# 04-LED-YELLOW.net
KiCad netlist of a schematic drawn in Altium Designer
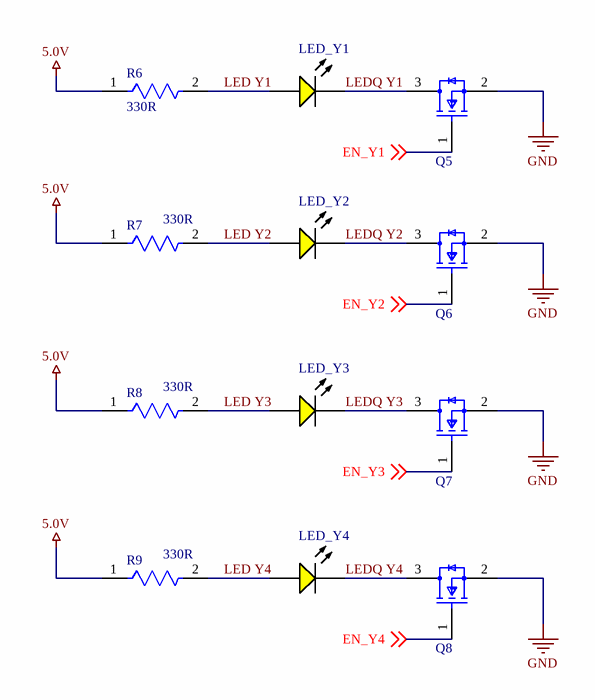
[diagram p0: 04-LED-YELLOW.SchDoc]

(export (version "E")
  (design (tool "Eeschema 10.0.6"))
  (components
    (comp (ref "LED_Y1")
      (value "SML-LX1206YC-TR")
      (footprint "LUMX-SML-LX1206YC-TR_V")
      (description "Yellow LED, Water Clear Len, 585 nm, 2.1 V, -40 to 85 degC, 2-Pin SMD, RoHS, Tape and Reel")
      (fields (field (name "MANUFACTURER") "Lumex"))
      (libsource (lib "Altium Content Vault") (part "LED-YELLOW-AK-2"))
    )
    (comp (ref "LED_Y2")
      (value "SML-LX1206YC-TR")
      (footprint "LUMX-SML-LX1206YC-TR_V")
      (description "Yellow LED, Water Clear Len, 585 nm, 2.1 V, -40 to 85 degC, 2-Pin SMD, RoHS, Tape and Reel")
      (fields (field (name "MANUFACTURER") "Lumex"))
      (libsource (lib "Altium Content Vault") (part "LED-YELLOW-AK-2"))
    )
    (comp (ref "LED_Y3")
      (value "SML-LX1206YC-TR")
      (footprint "LUMX-SML-LX1206YC-TR_V")
      (description "Yellow LED, Water Clear Len, 585 nm, 2.1 V, -40 to 85 degC, 2-Pin SMD, RoHS, Tape and Reel")
      (fields (field (name "MANUFACTURER") "Lumex"))
      (libsource (lib "Altium Content Vault") (part "LED-YELLOW-AK-2"))
    )
    (comp (ref "LED_Y4")
      (value "SML-LX1206YC-TR")
      (footprint "LUMX-SML-LX1206YC-TR_V")
      (description "Yellow LED, Water Clear Len, 585 nm, 2.1 V, -40 to 85 degC, 2-Pin SMD, RoHS, Tape and Reel")
      (fields (field (name "MANUFACTURER") "Lumex"))
      (libsource (lib "Altium Content Vault") (part "LED-YELLOW-AK-2"))
    )
    (comp (ref "Q5")
      (value "2N7002-7-F")
      (footprint "FP-SOT23-MFG")
      (description "MOSFET N-CH 60V 115MA SOT23-3")
      (fields (field (name "VOLTAGE") "60V"))
      (libsource (lib "Altium Content Vault") (part "3b9c635fedb024a5347a57b145af9cc"))
    )
    (comp (ref "Q6")
      (value "2N7002-7-F")
      (footprint "FP-SOT23-MFG")
      (description "MOSFET N-CH 60V 115MA SOT23-3")
      (fields (field (name "VOLTAGE") "60V"))
      (libsource (lib "Altium Content Vault") (part "3b9c635fedb024a5347a57b145af9cc"))
    )
    (comp (ref "Q7")
      (value "2N7002-7-F")
      (footprint "FP-SOT23-MFG")
      (description "MOSFET N-CH 60V 115MA SOT23-3")
      (fields (field (name "VOLTAGE") "60V"))
      (libsource (lib "Altium Content Vault") (part "3b9c635fedb024a5347a57b145af9cc"))
    )
    (comp (ref "Q8")
      (value "2N7002-7-F")
      (footprint "FP-SOT23-MFG")
      (description "MOSFET N-CH 60V 115MA SOT23-3")
      (fields (field (name "VOLTAGE") "60V"))
      (libsource (lib "Altium Content Vault") (part "3b9c635fedb024a5347a57b145af9cc"))
    )
    (comp (ref "R6")
      (value "CRCW1206330RFKEA")
      (footprint "FP-CRCW1206-e3-IPC_A")
      (description "RES Thick Film, 330Ω, 1%, 0.25W, 100ppm/°C, 1206")
      (fields (field (name "TOLERANCE") "1%") (field (name "RESISTANCE") "330R"))
      (libsource (lib "Altium Content Vault") (part "1029c3af85768c4190bb7ad29bc67b5"))
    )
    (comp (ref "R7")
      (value "CRCW1206330RFKEA")
      (footprint "FP-CRCW1206-e3-IPC_A")
      (description "RES Thick Film, 330Ω, 1%, 0.25W, 100ppm/°C, 1206")
      (fields (field (name "TOLERANCE") "1%") (field (name "RESISTANCE") "330R"))
      (libsource (lib "Altium Content Vault") (part "1029c3af85768c4190bb7ad29bc67b5"))
    )
    (comp (ref "R8")
      (value "CRCW1206330RFKEA")
      (footprint "FP-CRCW1206-e3-IPC_A")
      (description "RES Thick Film, 330Ω, 1%, 0.25W, 100ppm/°C, 1206")
      (fields (field (name "TOLERANCE") "1%") (field (name "RESISTANCE") "330R"))
      (libsource (lib "Altium Content Vault") (part "1029c3af85768c4190bb7ad29bc67b5"))
    )
    (comp (ref "R9")
      (value "CRCW1206330RFKEA")
      (footprint "FP-CRCW1206-e3-IPC_A")
      (description "RES Thick Film, 330Ω, 1%, 0.25W, 100ppm/°C, 1206")
      (fields (field (name "TOLERANCE") "1%") (field (name "RESISTANCE") "330R"))
      (libsource (lib "Altium Content Vault") (part "1029c3af85768c4190bb7ad29bc67b5"))
    )
  )
  (nets
    (net (code "1") (name "/LED Y1") (class "Default")
      (node (ref "LED_Y1") (pin "1") (pinfunction "A_1") (pintype "passive"))
      (node (ref "R6") (pin "2") (pinfunction "2_2") (pintype "passive"))
    )
    (net (code "2") (name "/LED Y2") (class "Default")
      (node (ref "LED_Y2") (pin "1") (pinfunction "A_1") (pintype "passive"))
      (node (ref "R7") (pin "2") (pinfunction "2_2") (pintype "passive"))
    )
    (net (code "3") (name "/LED Y3") (class "Default")
      (node (ref "LED_Y3") (pin "1") (pinfunction "A_1") (pintype "passive"))
      (node (ref "R8") (pin "2") (pinfunction "2_2") (pintype "passive"))
    )
    (net (code "4") (name "/LED Y4") (class "Default")
      (node (ref "LED_Y4") (pin "1") (pinfunction "A_1") (pintype "passive"))
      (node (ref "R9") (pin "2") (pinfunction "2_2") (pintype "passive"))
    )
    (net (code "5") (name "/LEDQ Y1") (class "Default")
      (node (ref "LED_Y1") (pin "2") (pinfunction "K_2") (pintype "passive"))
      (node (ref "Q5") (pin "3") (pinfunction "D_3") (pintype "passive"))
    )
    (net (code "6") (name "/LEDQ Y2") (class "Default")
      (node (ref "LED_Y2") (pin "2") (pinfunction "K_2") (pintype "passive"))
      (node (ref "Q6") (pin "3") (pinfunction "D_3") (pintype "passive"))
    )
    (net (code "7") (name "/LEDQ Y3") (class "Default")
      (node (ref "LED_Y3") (pin "2") (pinfunction "K_2") (pintype "passive"))
      (node (ref "Q7") (pin "3") (pinfunction "D_3") (pintype "passive"))
    )
    (net (code "8") (name "/LEDQ Y4") (class "Default")
      (node (ref "LED_Y4") (pin "2") (pinfunction "K_2") (pintype "passive"))
      (node (ref "Q8") (pin "3") (pinfunction "D_3") (pintype "passive"))
    )
    (net (code "9") (name "5.0V") (class "Default")
      (node (ref "R6") (pin "1") (pinfunction "1_1") (pintype "passive"))
      (node (ref "R7") (pin "1") (pinfunction "1_1") (pintype "passive"))
      (node (ref "R8") (pin "1") (pinfunction "1_1") (pintype "passive"))
      (node (ref "R9") (pin "1") (pinfunction "1_1") (pintype "passive"))
    )
    (net (code "10") (name "EN_Y1") (class "Default")
      (node (ref "Q5") (pin "1") (pinfunction "G_1") (pintype "passive"))
    )
    (net (code "11") (name "EN_Y2") (class "Default")
      (node (ref "Q6") (pin "1") (pinfunction "G_1") (pintype "passive"))
    )
    (net (code "12") (name "EN_Y3") (class "Default")
      (node (ref "Q7") (pin "1") (pinfunction "G_1") (pintype "passive"))
    )
    (net (code "13") (name "EN_Y4") (class "Default")
      (node (ref "Q8") (pin "1") (pinfunction "G_1") (pintype "passive"))
    )
    (net (code "14") (name "GND") (class "Default")
      (node (ref "Q5") (pin "2") (pinfunction "S_2") (pintype "passive"))
      (node (ref "Q6") (pin "2") (pinfunction "S_2") (pintype "passive"))
      (node (ref "Q7") (pin "2") (pinfunction "S_2") (pintype "passive"))
      (node (ref "Q8") (pin "2") (pinfunction "S_2") (pintype "passive"))
    )
  )
)
